# 12_SWITCH_LED.net
KiCad netlist of a schematic drawn in Altium Designer
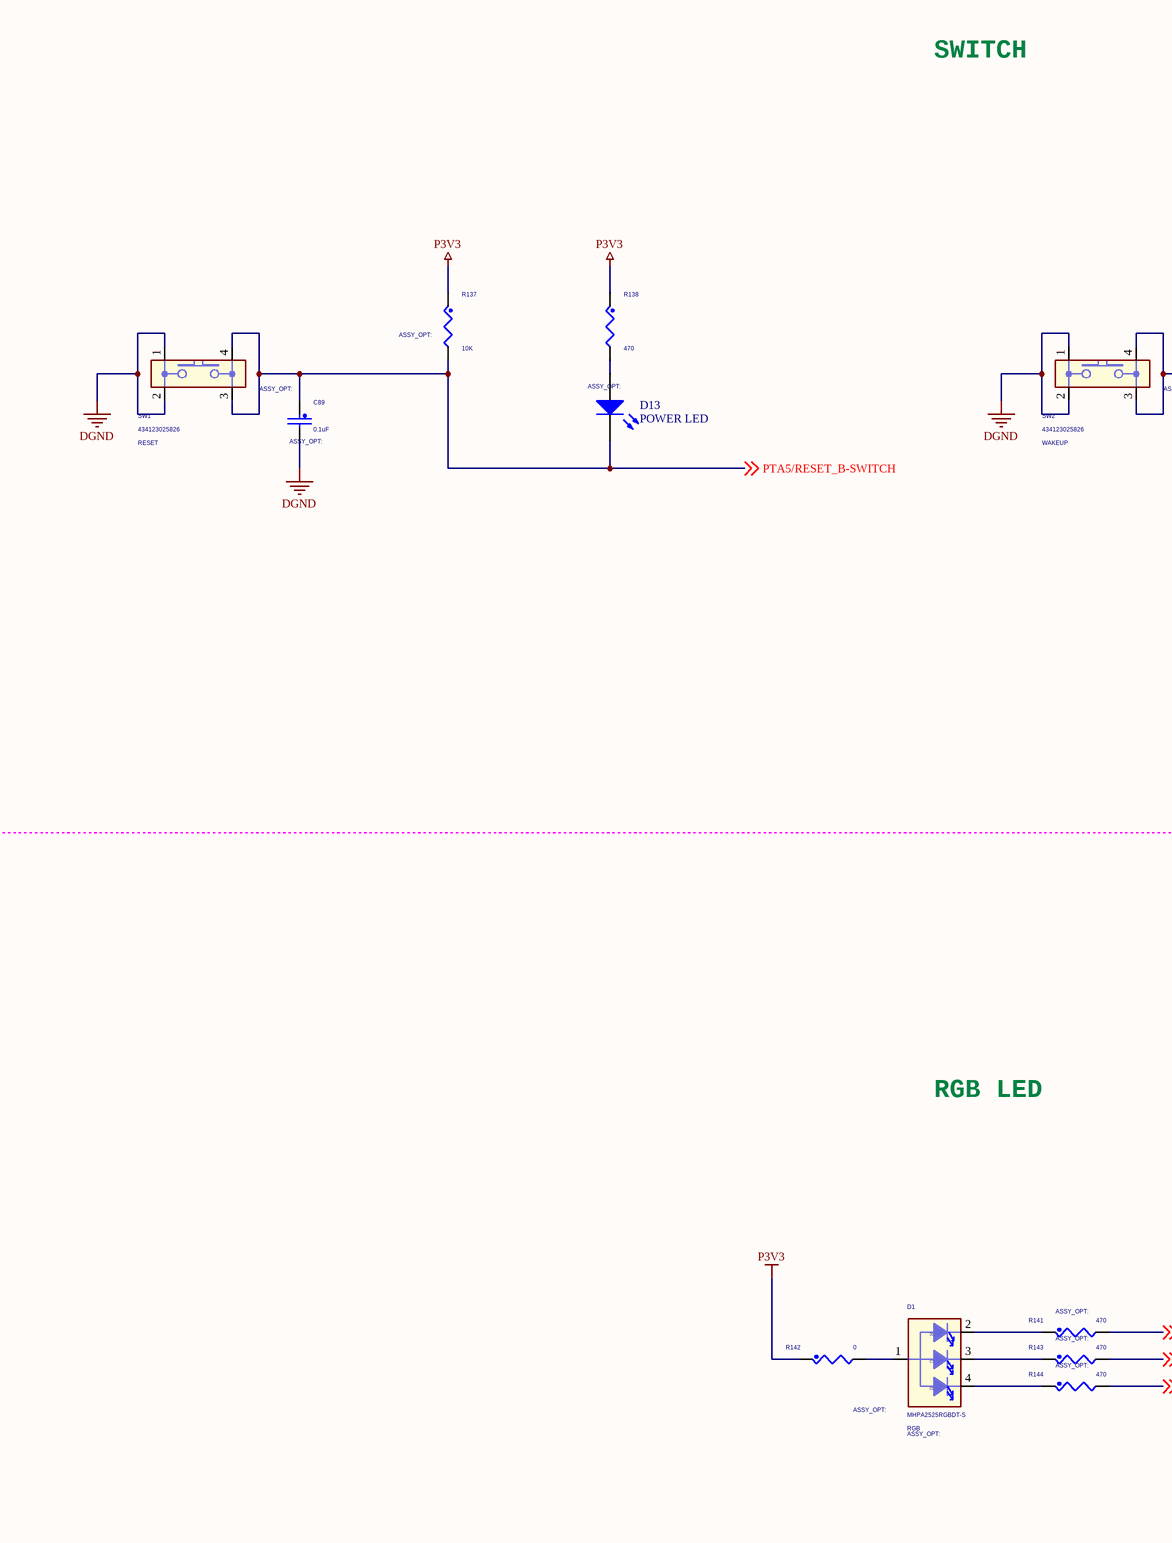
[diagram p0: 12 SWITCH & LED.SchDoc, left]
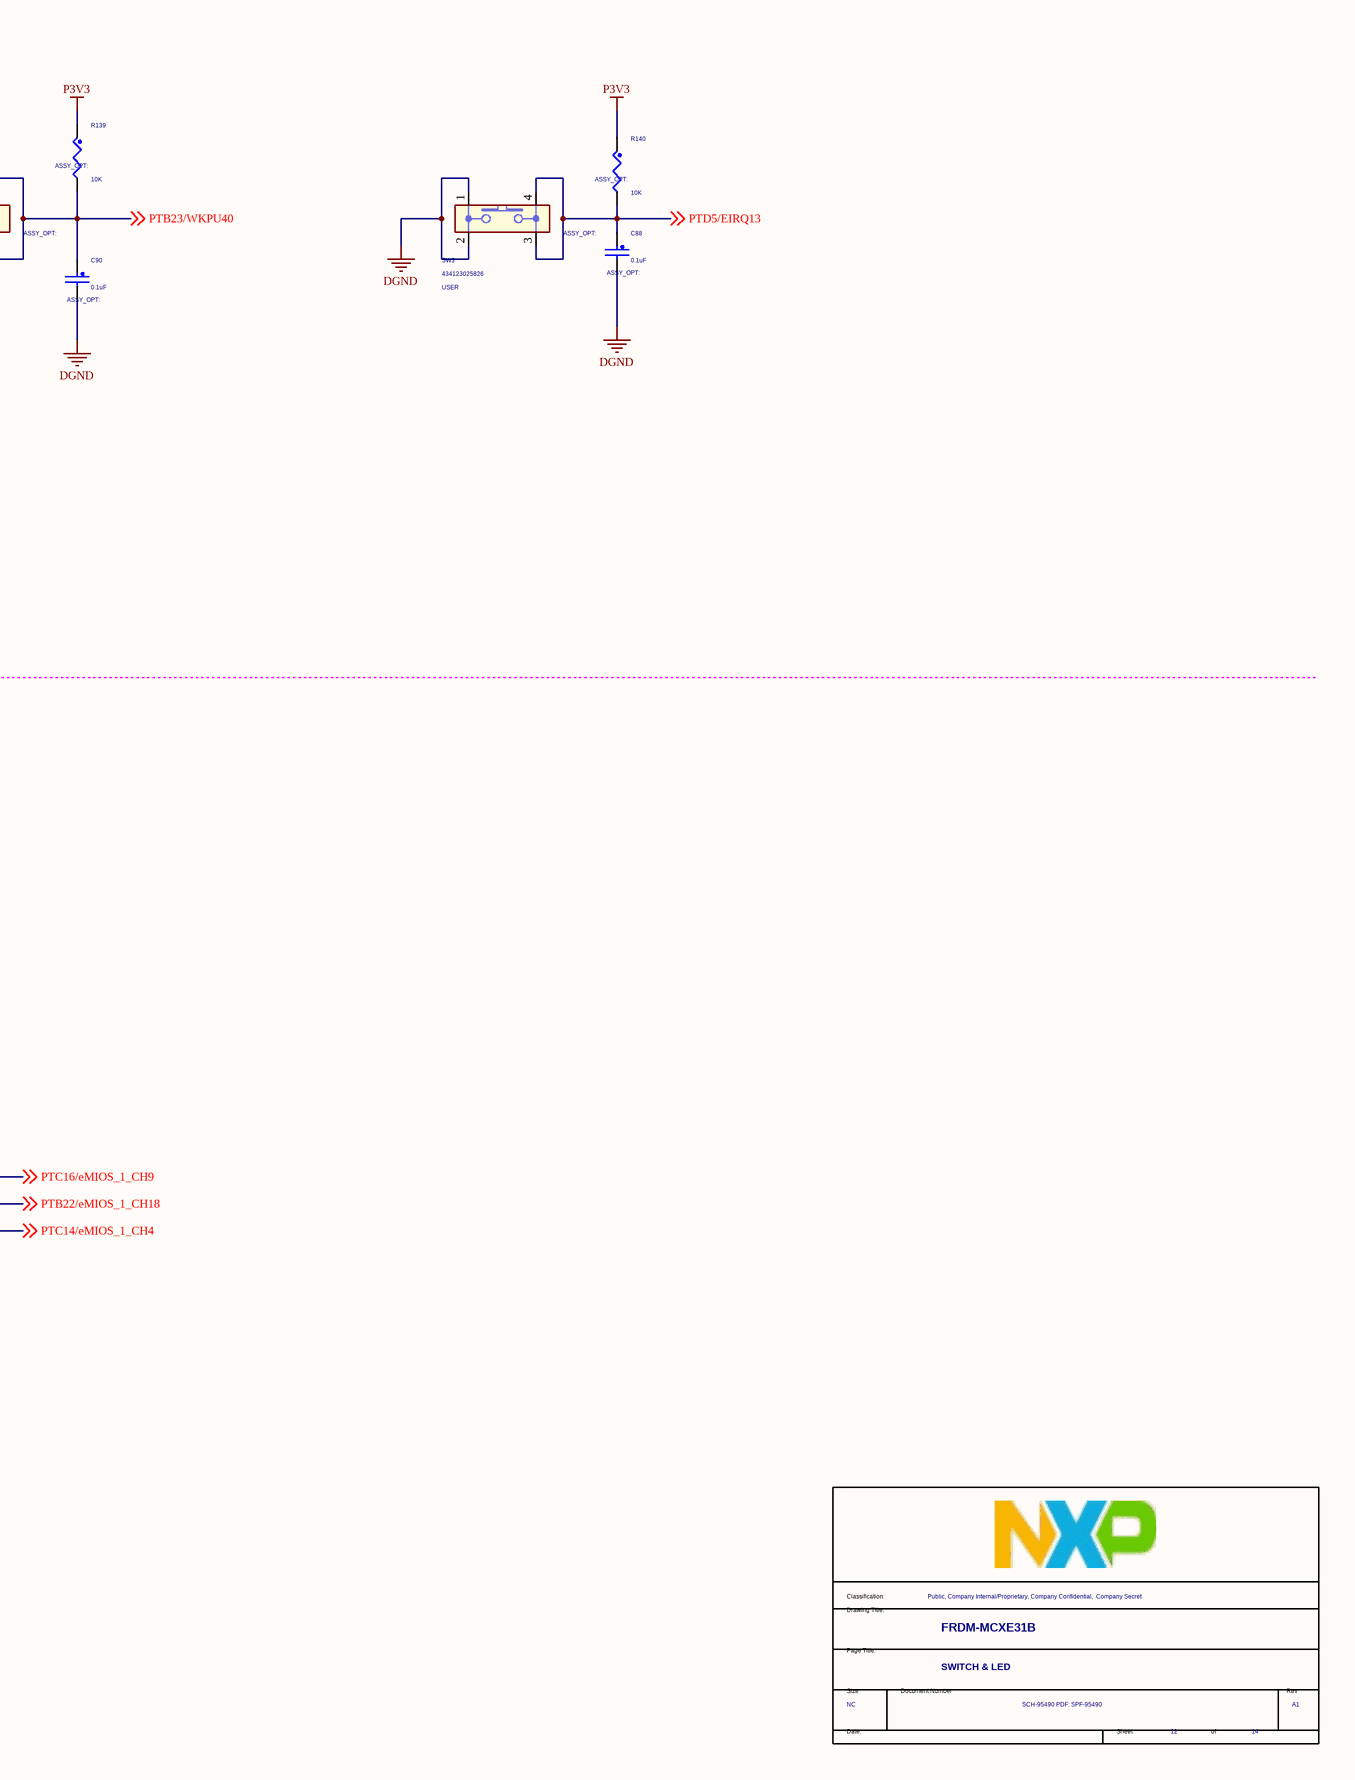
[diagram p1: 12 SWITCH & LED.SchDoc, right]

(export (version "E")
  (design (tool "Eeschema 10.0.6"))
  (components
    (comp (ref "C88")
      (value "0.1uF")
      (footprint "CC0402_25")
      (description "CAP CER 0.1UF 16V 10% X7R 0402")
      (fields (field (name "TOLERANCE") "10%") (field (name "VOLTAGE") "16V"))
      (libsource (lib "*") (part "CAP_NP"))
    )
    (comp (ref "C89")
      (value "0.1uF")
      (footprint "CC0402_25")
      (description "CAP CER 0.1UF 16V 10% X7R 0402")
      (fields (field (name "VOLTAGE") "16V") (field (name "TOLERANCE") "10%"))
      (libsource (lib "*") (part "CAP_NP"))
    )
    (comp (ref "C90")
      (value "0.1uF")
      (footprint "CC0402_25")
      (description "CAP CER 0.1UF 16V 10% X7R 0402")
      (fields (field (name "TOLERANCE") "10%") (field (name "VOLTAGE") "16V"))
      (libsource (lib "*") (part "CAP_NP"))
    )
    (comp (ref "D1")
      (value "RGB")
      (footprint "led4_2p7x2p6_sm")
      (description "LED RED/GRN/BL TRI 20/20/20MA SMT")
      (fields (field (name "SILK") "RGB") (field (name "MFG_PN01") "MHPA2525RGBDT-S"))
      (libsource (lib "*") (part "LRTBR48G_4P"))
    )
    (comp (ref "D13")
      (value "POWER LED")
      (footprint "LED 0603R")
      (libsource (lib "MyMiscellaneousDevice") (part "LED-SMT"))
    )
    (comp (ref "R137")
      (value "10K")
      (footprint "RC0402_25")
      (description "RES MF 10K 1/16W 5% 0402")
      (fields (field (name "TOLERANCE") "5%"))
      (libsource (lib "*") (part "RES"))
    )
    (comp (ref "R138")
      (value "470")
      (footprint "RC0402_25")
      (description "RES MF 470 OHM 1/16W 5% 0402")
      (fields (field (name "TOLERANCE") "5%"))
      (libsource (lib "*") (part "RES"))
    )
    (comp (ref "R139")
      (value "10K")
      (footprint "RC0402_25")
      (description "RES MF 10K 1/16W 5% 0402")
      (fields (field (name "TOLERANCE") "5%"))
      (libsource (lib "*") (part "RES"))
    )
    (comp (ref "R140")
      (value "10K")
      (footprint "RC0402_25")
      (description "RES MF 10K 1/16W 5% 0402")
      (fields (field (name "TOLERANCE") "5%"))
      (libsource (lib "*") (part "RES"))
    )
    (comp (ref "R141")
      (value "470")
      (footprint "RC0402_25")
      (description "RES MF 470 OHM 1/16W 5% 0402")
      (fields (field (name "TOLERANCE") "5%"))
      (libsource (lib "*") (part "RES"))
    )
    (comp (ref "R142")
      (value "0")
      (footprint "RC0603_OV")
      (description "RES MF ZERO OHM 1/10W -- 0603")
      (libsource (lib "*") (part "RES"))
    )
    (comp (ref "R143")
      (value "470")
      (footprint "RC0402_25")
      (description "RES MF 470 OHM 1/16W 5% 0402")
      (fields (field (name "TOLERANCE") "5%"))
      (libsource (lib "*") (part "RES"))
    )
    (comp (ref "R144")
      (value "470")
      (footprint "RC0402_25")
      (description "RES MF 470 OHM 1/16W 5% 0402")
      (fields (field (name "TOLERANCE") "5%"))
      (libsource (lib "*") (part "RES"))
    )
    (comp (ref "SW1")
      (value "SW SPST NO")
      (footprint "SW-SMD_4P-L5.1-W5.1-P3.70-LS6.5-TL_H1.5")
      (description "SW SP PB 50mA 16V SMT")
      (fields (field (name "SILK") "RESET") (field (name "MFG_PN01") "434123025826"))
      (libsource (lib "*") (part "SW_PSHBT_SPST_2"))
    )
    (comp (ref "SW2")
      (value "SW SPST NO")
      (footprint "SW-SMD_4P-L5.1-W5.1-P3.70-LS6.5-TL_H1.5")
      (description "SW SP PB 50mA 16V SMT")
      (fields (field (name "MFG_PN01") "434123025826") (field (name "SILK") "WAKEUP"))
      (libsource (lib "*") (part "SW_PSHBT_SPST_2"))
    )
    (comp (ref "SW3")
      (value "SW SPST NO")
      (footprint "SW-SMD_4P-L5.1-W5.1-P3.70-LS6.5-TL_H1.5")
      (description "SW SP PB 50mA 16V SMT")
      (fields (field (name "SILK") "USER") (field (name "MFG_PN01") "434123025826"))
      (libsource (lib "*") (part "SW_PSHBT_SPST_2"))
    )
  )
  (nets
    (net (code "1") (name "DGND") (class "Default")
      (node (ref "C88") (pin "2") (pinfunction "2_2") (pintype "passive"))
      (node (ref "C89") (pin "2") (pinfunction "2_2") (pintype "passive"))
      (node (ref "C90") (pin "2") (pinfunction "2_2") (pintype "passive"))
      (node (ref "SW1") (pin "1") (pinfunction "1_1") (pintype "passive"))
      (node (ref "SW1") (pin "2") (pinfunction "2_2") (pintype "passive"))
      (node (ref "SW2") (pin "1") (pinfunction "1_1") (pintype "passive"))
      (node (ref "SW2") (pin "2") (pinfunction "2_2") (pintype "passive"))
      (node (ref "SW3") (pin "1") (pinfunction "1_1") (pintype "passive"))
      (node (ref "SW3") (pin "2") (pinfunction "2_2") (pintype "passive"))
    )
    (net (code "2") (name "Net-(D1-ANODE)") (class "Default")
      (node (ref "D1") (pin "1") (pinfunction "ANODE_1") (pintype "passive"))
      (node (ref "R142") (pin "2") (pinfunction "2_2") (pintype "passive"))
    )
    (net (code "3") (name "Net-(D1-CATHODE1)") (class "Default")
      (node (ref "D1") (pin "2") (pinfunction "CATHODE1_2") (pintype "passive"))
      (node (ref "R141") (pin "1") (pinfunction "1_1") (pintype "passive"))
    )
    (net (code "4") (name "Net-(D1-CATHODE2)") (class "Default")
      (node (ref "D1") (pin "3") (pinfunction "CATHODE2_3") (pintype "passive"))
      (node (ref "R143") (pin "1") (pinfunction "1_1") (pintype "passive"))
    )
    (net (code "5") (name "Net-(D1-CATHODE3)") (class "Default")
      (node (ref "D1") (pin "4") (pinfunction "CATHODE3_4") (pintype "passive"))
      (node (ref "R144") (pin "1") (pinfunction "1_1") (pintype "passive"))
    )
    (net (code "6") (name "Net-(D13-A)") (class "Default")
      (node (ref "D13") (pin "1") (pinfunction "A_1") (pintype "passive"))
      (node (ref "R138") (pin "2") (pinfunction "2_2") (pintype "passive"))
    )
    (net (code "7") (name "P3V3") (class "Default")
      (node (ref "R137") (pin "1") (pinfunction "1_1") (pintype "passive"))
      (node (ref "R138") (pin "1") (pinfunction "1_1") (pintype "passive"))
      (node (ref "R139") (pin "1") (pinfunction "1_1") (pintype "passive"))
      (node (ref "R140") (pin "1") (pinfunction "1_1") (pintype "passive"))
      (node (ref "R142") (pin "1") (pinfunction "1_1") (pintype "passive"))
    )
    (net (code "8") (name "PTA5{slash}RESET_B-SWITCH") (class "Default")
      (node (ref "C89") (pin "1") (pinfunction "1_1") (pintype "passive"))
      (node (ref "D13") (pin "2") (pinfunction "K_2") (pintype "passive"))
      (node (ref "R137") (pin "2") (pinfunction "2_2") (pintype "passive"))
      (node (ref "SW1") (pin "3") (pinfunction "3_3") (pintype "passive"))
      (node (ref "SW1") (pin "4") (pinfunction "4_4") (pintype "passive"))
    )
    (net (code "9") (name "PTB22{slash}eMIOS_1_CH18") (class "Default")
      (node (ref "R143") (pin "2") (pinfunction "2_2") (pintype "passive"))
    )
    (net (code "10") (name "PTB23{slash}WKPU40") (class "Default")
      (node (ref "C90") (pin "1") (pinfunction "1_1") (pintype "passive"))
      (node (ref "R139") (pin "2") (pinfunction "2_2") (pintype "passive"))
      (node (ref "SW2") (pin "3") (pinfunction "3_3") (pintype "passive"))
      (node (ref "SW2") (pin "4") (pinfunction "4_4") (pintype "passive"))
    )
    (net (code "11") (name "PTC14{slash}eMIOS_1_CH4") (class "Default")
      (node (ref "R144") (pin "2") (pinfunction "2_2") (pintype "passive"))
    )
    (net (code "12") (name "PTC16{slash}eMIOS_1_CH9") (class "Default")
      (node (ref "R141") (pin "2") (pinfunction "2_2") (pintype "passive"))
    )
    (net (code "13") (name "PTD5{slash}EIRQ13") (class "Default")
      (node (ref "C88") (pin "1") (pinfunction "1_1") (pintype "passive"))
      (node (ref "R140") (pin "2") (pinfunction "2_2") (pintype "passive"))
      (node (ref "SW3") (pin "3") (pinfunction "3_3") (pintype "passive"))
      (node (ref "SW3") (pin "4") (pinfunction "4_4") (pintype "passive"))
    )
  )
)
